# QSFP.net
KiCad netlist of a schematic drawn in Altium Designer
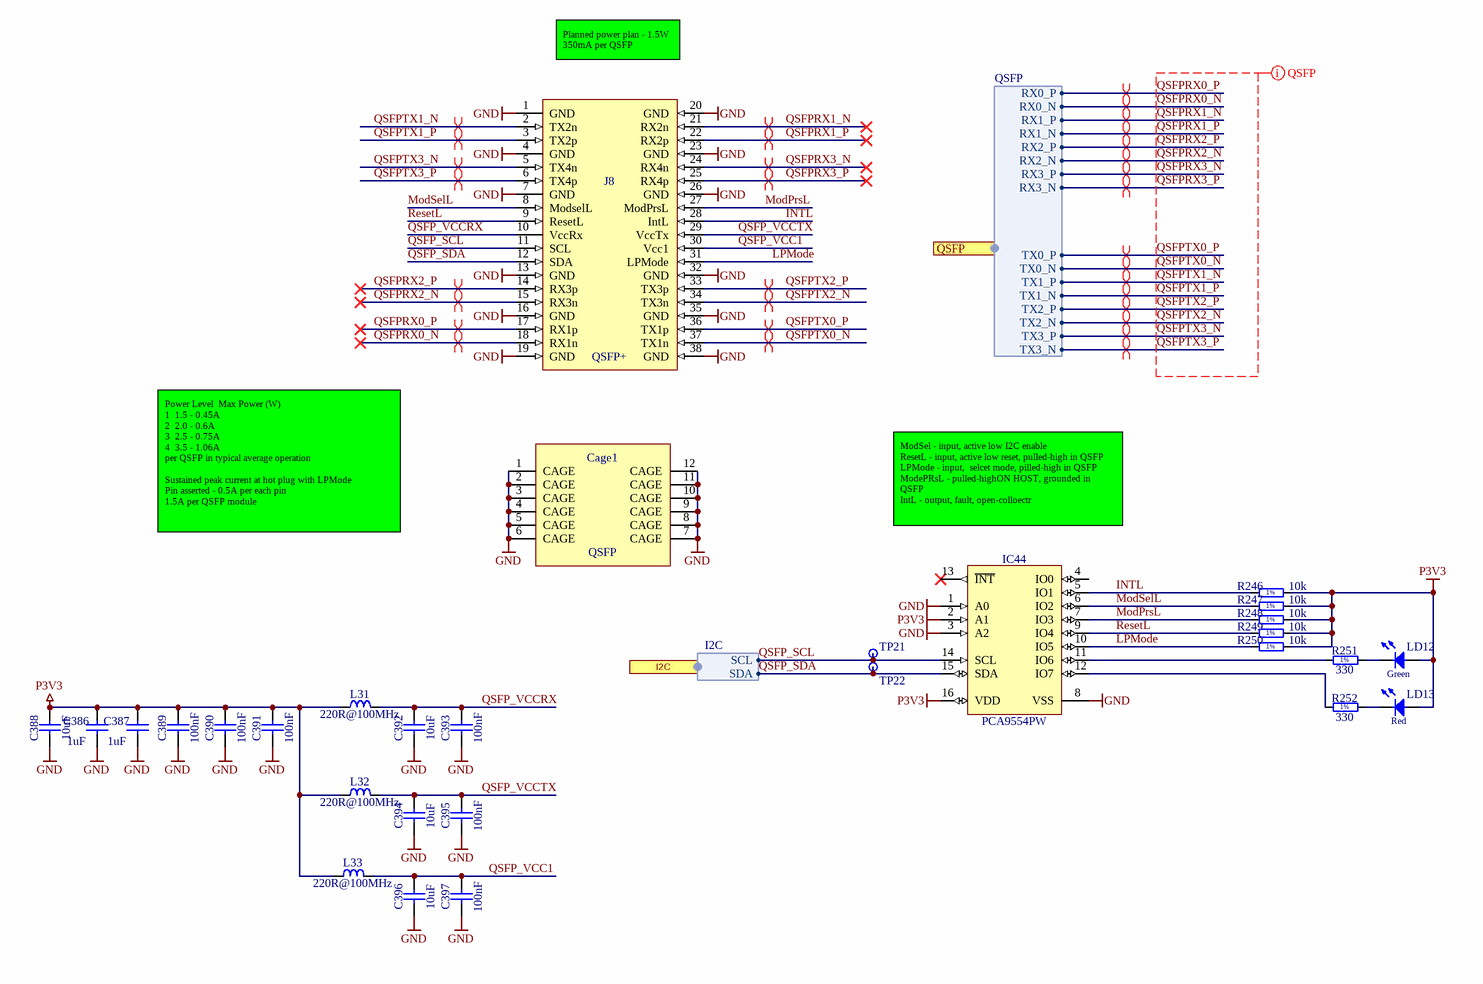
[diagram p0: QSFP.SchDoc]

(export (version "E")
  (design (tool "Eeschema 10.0.6"))
  (components
    (comp (ref "C386")
      (value "1uF")
      (footprint "CAPC1005X55N")
      (description "Non-polarised capacitor")
      (fields
        (field (name "MANUFACTURER PART NUMBER") "CC0402_1UF_16V_10%_X5R")
        (field (name "MANUFACTURER") "GENERIC")
        (field (name "AUTHOR") "CERN DEM JLC")
      )
      (libsource (lib "Capacitors") (part "Capacitor - non polarized"))
    )
    (comp (ref "C387")
      (value "1uF")
      (footprint "CAPC1005X55N")
      (description "Non-polarised capacitor")
      (fields
        (field (name "MANUFACTURER PART NUMBER") "CC0402_1UF_16V_10%_X5R")
        (field (name "MANUFACTURER") "GENERIC")
        (field (name "AUTHOR") "CERN DEM JLC")
      )
      (libsource (lib "Capacitors") (part "Capacitor - non polarized"))
    )
    (comp (ref "C388")
      (value "10uF")
      (footprint "CAPC2012X135N")
      (description "Non-polarised capacitor")
      (fields
        (field (name "PART NUMBER") "CC0805_10UF_10V_10%_X7R")
        (field (name "VOLTAGE") "10V")
        (field (name "AUTHOR") "CERN DEM JLC")
      )
      (libsource (lib "Capacitors") (part "Capacitor - non polarized"))
    )
    (comp (ref "C389")
      (value "100nF")
      (footprint "CAPC1005X55N")
      (description "Non-polarised capacitor")
      (fields
        (field (name "PART NUMBER") "CC0402_100NF_16V_10%_X5R")
        (field (name "VOLTAGE") "16V")
        (field (name "AUTHOR") "CERN DEM JLC")
      )
      (libsource (lib "Capacitors") (part "Capacitor - non polarized"))
    )
    (comp (ref "C390")
      (value "100nF")
      (footprint "CAPC1005X55N")
      (description "Non-polarised capacitor")
      (fields
        (field (name "PART NUMBER") "CC0402_100NF_16V_10%_X5R")
        (field (name "VOLTAGE") "16V")
        (field (name "AUTHOR") "CERN DEM JLC")
      )
      (libsource (lib "Capacitors") (part "Capacitor - non polarized"))
    )
    (comp (ref "C391")
      (value "100nF")
      (footprint "CAPC1005X55N")
      (description "Non-polarised capacitor")
      (fields
        (field (name "PART NUMBER") "CC0402_100NF_16V_10%_X5R")
        (field (name "VOLTAGE") "16V")
        (field (name "AUTHOR") "CERN DEM JLC")
      )
      (libsource (lib "Capacitors") (part "Capacitor - non polarized"))
    )
    (comp (ref "C392")
      (value "10uF")
      (footprint "CAPC2012X135N")
      (description "Non-polarised capacitor")
      (fields
        (field (name "PART NUMBER") "CC0805_10UF_10V_10%_X7R")
        (field (name "VOLTAGE") "10V")
        (field (name "AUTHOR") "CERN DEM JLC")
      )
      (libsource (lib "Capacitors") (part "Capacitor - non polarized"))
    )
    (comp (ref "C393")
      (value "100nF")
      (footprint "CAPC1005X55N")
      (description "Non-polarised capacitor")
      (fields
        (field (name "PART NUMBER") "CC0402_100NF_16V_10%_X5R")
        (field (name "VOLTAGE") "16V")
        (field (name "AUTHOR") "CERN DEM JLC")
      )
      (libsource (lib "Capacitors") (part "Capacitor - non polarized"))
    )
    (comp (ref "C394")
      (value "10uF")
      (footprint "CAPC2012X135N")
      (description "Non-polarised capacitor")
      (fields
        (field (name "PART NUMBER") "CC0805_10UF_10V_10%_X7R")
        (field (name "VOLTAGE") "10V")
        (field (name "AUTHOR") "CERN DEM JLC")
      )
      (libsource (lib "Capacitors") (part "Capacitor - non polarized"))
    )
    (comp (ref "C395")
      (value "100nF")
      (footprint "CAPC1005X55N")
      (description "Non-polarised capacitor")
      (fields
        (field (name "PART NUMBER") "CC0402_100NF_16V_10%_X5R")
        (field (name "VOLTAGE") "16V")
        (field (name "AUTHOR") "CERN DEM JLC")
      )
      (libsource (lib "Capacitors") (part "Capacitor - non polarized"))
    )
    (comp (ref "C396")
      (value "10uF")
      (footprint "CAPC2012X135N")
      (description "Non-polarised capacitor")
      (fields
        (field (name "PART NUMBER") "CC0805_10UF_10V_10%_X7R")
        (field (name "VOLTAGE") "10V")
        (field (name "AUTHOR") "CERN DEM JLC")
      )
      (libsource (lib "Capacitors") (part "Capacitor - non polarized"))
    )
    (comp (ref "C397")
      (value "100nF")
      (footprint "CAPC1005X55N")
      (description "Non-polarised capacitor")
      (fields
        (field (name "PART NUMBER") "CC0402_100NF_16V_10%_X5R")
        (field (name "VOLTAGE") "16V")
        (field (name "AUTHOR") "CERN DEM JLC")
      )
      (libsource (lib "Capacitors") (part "Capacitor - non polarized"))
    )
    (comp (ref "Cage1")
      (value "QSFP")
      (footprint "TYCO_1888617-1")
      (description "QSFP 1x1 Cage (12Pins)")
      (fields
        (field (name "PART NUMBER") "TYCO_1888617-1")
        (field (name "MANUFACTURER") "TYCO ELECTRONICS")
        (field (name "AUTHOR") "CERN DEM JLC")
      )
      (libsource (lib "Connectors") (part "QSFP 1x1 Cage (12Pins)"))
    )
    (comp (ref "IC44")
      (value "PCA9554PW")
      (footprint "SOP65P640X110-16N")
      (description "8-Bit I2C-Bus and SMBus I/O Port with Interrupt")
      (fields (field (name "MANUFACTURER") "NXP SEMICONDUCTORS") (field (name "AUTHOR") "CERN DEM JLC"))
      (libsource (lib "ICs And Semiconductors") (part "PCA9554PW"))
    )
    (comp (ref "J8")
      (value "QSFP+")
      (footprint "TYCO_2110819-1")
      (description "38Position QSFP Connector  (Quad Small Form-factor Pluggable)")
      (fields
        (field (name "PART NUMBER") "TYCO_2110819-1")
        (field (name "MANUFACTURER") "TYCO ELECTRONICS")
        (field (name "AUTHOR") "CERN DEM JLC")
      )
      (libsource (lib "Connectors") (part "QSFP+x1"))
    )
    (comp (ref "L31")
      (value "220R@100MHz")
      (footprint "INDC2012X105N")
      (description "Inductor")
      (fields
        (field (name "PART NUMBER") "IND0805_MURATA_BLM21PG221SN1D")
        (field (name "POWER") "2A")
        (field (name "AUTHOR") "CERN DEM JLC")
      )
      (libsource (lib "Inductors & Transformers") (part "Inductor"))
    )
    (comp (ref "L32")
      (value "220R@100MHz")
      (footprint "INDC2012X105N")
      (description "Inductor")
      (fields
        (field (name "PART NUMBER") "IND0805_MURATA_BLM21PG221SN1D")
        (field (name "POWER") "2A")
        (field (name "AUTHOR") "CERN DEM JLC")
      )
      (libsource (lib "Inductors & Transformers") (part "Inductor"))
    )
    (comp (ref "L33")
      (value "220R@100MHz")
      (footprint "INDC2012X105N")
      (description "Inductor")
      (fields
        (field (name "PART NUMBER") "IND0805_MURATA_BLM21PG221SN1D")
        (field (name "POWER") "2A")
        (field (name "AUTHOR") "CERN DEM JLC")
      )
      (libsource (lib "Inductors & Transformers") (part "Inductor"))
    )
    (comp (ref "LD12")
      (value "Green")
      (footprint "LED_AVAGO_HSME-C120")
      (description "LED Green 1C 2A")
      (fields
        (field (name "MANUFACTURER PART NUMBER") "HSME-C120")
        (field (name "MANUFACTURER") "AVAGO TECHNOLOGIES")
        (field (name "AUTHOR") "CERN DEM JMW")
      )
      (libsource (lib "ICs And Semiconductors") (part "LED Green 1C 2A"))
    )
    (comp (ref "LD13")
      (value "Red")
      (footprint "LED_AVAGO_HSMC-C120")
      (description "LED Red 1C 2A")
      (fields
        (field (name "PART NUMBER") "LED_AVAGO_HSMC-C120")
        (field (name "MANUFACTURER") "AVAGO TECHNOLOGIES")
        (field (name "AUTHOR") "CERN DEM JMW")
      )
      (libsource (lib "ICs And Semiconductors") (part "LED Red 1C 2A"))
    )
    (comp (ref "R246")
      (value "10k")
      (footprint "RESC1005X40N")
      (description "Resistor - 1%")
      (fields
        (field (name "MANUFACTURER PART NUMBER") "R0402_10K_1%_0.0625W_100PPM")
        (field (name "MANUFACTURER") "GENERIC")
        (field (name "AUTHOR") "CERN DEM JLC")
      )
      (libsource (lib "Resistors") (part "Resistor - 1%"))
    )
    (comp (ref "R247")
      (value "10k")
      (footprint "RESC1005X40N")
      (description "Resistor - 1%")
      (fields
        (field (name "MANUFACTURER PART NUMBER") "R0402_10K_1%_0.0625W_100PPM")
        (field (name "MANUFACTURER") "GENERIC")
        (field (name "AUTHOR") "CERN DEM JLC")
      )
      (libsource (lib "Resistors") (part "Resistor - 1%"))
    )
    (comp (ref "R248")
      (value "10k")
      (footprint "RESC1005X40N")
      (description "Resistor - 1%")
      (fields
        (field (name "MANUFACTURER PART NUMBER") "R0402_10K_1%_0.0625W_100PPM")
        (field (name "MANUFACTURER") "GENERIC")
        (field (name "AUTHOR") "CERN DEM JLC")
      )
      (libsource (lib "Resistors") (part "Resistor - 1%"))
    )
    (comp (ref "R249")
      (value "10k")
      (footprint "RESC1005X40N")
      (description "Resistor - 1%")
      (fields
        (field (name "MANUFACTURER PART NUMBER") "R0402_10K_1%_0.0625W_100PPM")
        (field (name "MANUFACTURER") "GENERIC")
        (field (name "AUTHOR") "CERN DEM JLC")
      )
      (libsource (lib "Resistors") (part "Resistor - 1%"))
    )
    (comp (ref "R250")
      (value "10k")
      (footprint "RESC1005X40N")
      (description "Resistor - 1%")
      (fields
        (field (name "MANUFACTURER PART NUMBER") "R0402_10K_1%_0.0625W_100PPM")
        (field (name "MANUFACTURER") "GENERIC")
        (field (name "AUTHOR") "CERN DEM JLC")
      )
      (libsource (lib "Resistors") (part "Resistor - 1%"))
    )
    (comp (ref "R251")
      (value "330")
      (footprint "RESC1005X40N")
      (description "Resistor - 1%")
      (fields
        (field (name "MANUFACTURER PART NUMBER") "R0402_330R_1%_0.0625W_100PPM")
        (field (name "MANUFACTURER") "GENERIC")
        (field (name "AUTHOR") "CERN DEM JLC")
      )
      (libsource (lib "Resistors") (part "Resistor - 1%"))
    )
    (comp (ref "R252")
      (value "330")
      (footprint "RESC1005X40N")
      (description "Resistor - 1%")
      (fields
        (field (name "MANUFACTURER PART NUMBER") "R0402_330R_1%_0.0625W_100PPM")
        (field (name "MANUFACTURER") "GENERIC")
        (field (name "AUTHOR") "CERN DEM JLC")
      )
      (libsource (lib "Resistors") (part "Resistor - 1%"))
    )
    (comp (ref "TP21")
      (value "Test Point")
      (footprint "TPS127")
      (fields (field (name "PART NUMBER") "SMD_PAD_1.27X1.27MM") (field (name "AUTHOR") "CERN DEM JLC"))
      (libsource (lib "Eletro-mechanical") (part "Test Point"))
    )
    (comp (ref "TP22")
      (value "Test Point")
      (footprint "TPS127")
      (fields (field (name "PART NUMBER") "SMD_PAD_1.27X1.27MM") (field (name "AUTHOR") "CERN DEM JLC"))
      (libsource (lib "Eletro-mechanical") (part "Test Point"))
    )
  )
  (nets
    (net (code "3") (name "/INTL") (class "Default")
      (node (ref "IC44") (pin "5") (pinfunction "IO1_5") (pintype "bidirectional"))
      (node (ref "J8") (pin "28") (pinfunction "IntL_28") (pintype "input"))
      (node (ref "R246") (pin "1") (pinfunction "1_1") (pintype "passive"))
    )
    (net (code "4") (name "/LPMode") (class "Default")
      (node (ref "IC44") (pin "10") (pinfunction "IO5_10") (pintype "bidirectional"))
      (node (ref "J8") (pin "31") (pinfunction "LPMode_31") (pintype "input"))
      (node (ref "R250") (pin "1") (pinfunction "1_1") (pintype "passive"))
    )
    (net (code "5") (name "/ModPrsL") (class "Default")
      (node (ref "IC44") (pin "7") (pinfunction "IO3_7") (pintype "bidirectional"))
      (node (ref "J8") (pin "27") (pinfunction "ModPrsL_27") (pintype "input"))
      (node (ref "R248") (pin "1") (pinfunction "1_1") (pintype "passive"))
    )
    (net (code "6") (name "/ModSelL") (class "Default")
      (node (ref "IC44") (pin "6") (pinfunction "IO2_6") (pintype "bidirectional"))
      (node (ref "J8") (pin "8") (pinfunction "ModselL_8") (pintype "input"))
      (node (ref "R247") (pin "1") (pinfunction "1_1") (pintype "passive"))
    )
    (net (code "7") (name "/QSFPRX0_N") (class "Default")
      (node (ref "J8") (pin "18") (pinfunction "RX1n_18") (pintype "input+no_connect"))
    )
    (net (code "8") (name "/QSFPRX0_P") (class "Default")
      (node (ref "J8") (pin "17") (pinfunction "RX1p_17") (pintype "input+no_connect"))
    )
    (net (code "9") (name "/QSFPRX1_N") (class "Default")
      (node (ref "J8") (pin "21") (pinfunction "RX2n_21") (pintype "input+no_connect"))
    )
    (net (code "10") (name "/QSFPRX1_P") (class "Default")
      (node (ref "J8") (pin "22") (pinfunction "RX2p_22") (pintype "input+no_connect"))
    )
    (net (code "11") (name "/QSFPRX2_N") (class "Default")
      (node (ref "J8") (pin "15") (pinfunction "RX3n_15") (pintype "input+no_connect"))
    )
    (net (code "12") (name "/QSFPRX2_P") (class "Default")
      (node (ref "J8") (pin "14") (pinfunction "RX3p_14") (pintype "input+no_connect"))
    )
    (net (code "13") (name "/QSFPRX3_N") (class "Default")
      (node (ref "J8") (pin "24") (pinfunction "RX4n_24") (pintype "input"))
    )
    (net (code "14") (name "/QSFPRX3_P") (class "Default")
      (node (ref "J8") (pin "25") (pinfunction "RX4p_25") (pintype "input+no_connect"))
    )
    (net (code "15") (name "/QSFPTX0_N") (class "Default")
      (node (ref "J8") (pin "37") (pinfunction "TX1n_37") (pintype "input"))
    )
    (net (code "16") (name "/QSFPTX0_P") (class "Default")
      (node (ref "J8") (pin "36") (pinfunction "TX1p_36") (pintype "input"))
    )
    (net (code "17") (name "/QSFPTX1_N") (class "Default")
      (node (ref "J8") (pin "2") (pinfunction "TX2n_2") (pintype "input"))
    )
    (net (code "18") (name "/QSFPTX1_P") (class "Default")
      (node (ref "J8") (pin "3") (pinfunction "TX2p_3") (pintype "input"))
    )
    (net (code "19") (name "/QSFPTX2_N") (class "Default")
      (node (ref "J8") (pin "34") (pinfunction "TX3n_34") (pintype "input"))
    )
    (net (code "20") (name "/QSFPTX2_P") (class "Default")
      (node (ref "J8") (pin "33") (pinfunction "TX3p_33") (pintype "input"))
    )
    (net (code "21") (name "/QSFPTX3_N") (class "Default")
      (node (ref "J8") (pin "5") (pinfunction "TX4n_5") (pintype "input"))
    )
    (net (code "22") (name "/QSFPTX3_P") (class "Default")
      (node (ref "J8") (pin "6") (pinfunction "TX4p_6") (pintype "input"))
    )
    (net (code "23") (name "/QSFP_SCL") (class "Default")
      (node (ref "IC44") (pin "14") (pinfunction "SCL_14") (pintype "input"))
      (node (ref "J8") (pin "11") (pinfunction "SCL_11") (pintype "input"))
      (node (ref "TP21") (pin "1") (pinfunction "1_1") (pintype "bidirectional"))
    )
    (net (code "24") (name "/QSFP_SDA") (class "Default")
      (node (ref "IC44") (pin "15") (pinfunction "SDA_15") (pintype "bidirectional"))
      (node (ref "J8") (pin "12") (pinfunction "SDA_12") (pintype "input"))
      (node (ref "TP22") (pin "1") (pinfunction "1_1") (pintype "bidirectional"))
    )
    (net (code "25") (name "/QSFP_VCC1") (class "Default")
      (node (ref "C396") (pin "2") (pinfunction "2_2") (pintype "passive"))
      (node (ref "C397") (pin "2") (pinfunction "2_2") (pintype "passive"))
      (node (ref "J8") (pin "30") (pinfunction "Vcc1_30") (pintype "input"))
      (node (ref "L33") (pin "2") (pinfunction "2_2") (pintype "passive"))
    )
    (net (code "26") (name "/QSFP_VCCRX") (class "Default")
      (node (ref "C392") (pin "2") (pinfunction "2_2") (pintype "passive"))
      (node (ref "C393") (pin "2") (pinfunction "2_2") (pintype "passive"))
      (node (ref "J8") (pin "10") (pinfunction "VccRx_10") (pintype "power_in"))
      (node (ref "L31") (pin "2") (pinfunction "2_2") (pintype "passive"))
    )
    (net (code "27") (name "/QSFP_VCCTX") (class "Default")
      (node (ref "C394") (pin "2") (pinfunction "2_2") (pintype "passive"))
      (node (ref "C395") (pin "2") (pinfunction "2_2") (pintype "passive"))
      (node (ref "J8") (pin "29") (pinfunction "VccTx_29") (pintype "input"))
      (node (ref "L32") (pin "2") (pinfunction "2_2") (pintype "passive"))
    )
    (net (code "28") (name "/ResetL") (class "Default")
      (node (ref "IC44") (pin "9") (pinfunction "IO4_9") (pintype "bidirectional"))
      (node (ref "J8") (pin "9") (pinfunction "ResetL_9") (pintype "input"))
      (node (ref "R249") (pin "1") (pinfunction "1_1") (pintype "passive"))
    )
    (net (code "31") (name "GND") (class "Default")
      (node (ref "C386") (pin "2") (pinfunction "2_2") (pintype "passive"))
      (node (ref "C387") (pin "2") (pinfunction "2_2") (pintype "passive"))
      (node (ref "C388") (pin "1") (pinfunction "1_1") (pintype "passive"))
      (node (ref "C389") (pin "1") (pinfunction "1_1") (pintype "passive"))
      (node (ref "C390") (pin "1") (pinfunction "1_1") (pintype "passive"))
      (node (ref "C391") (pin "1") (pinfunction "1_1") (pintype "passive"))
      (node (ref "C392") (pin "1") (pinfunction "1_1") (pintype "passive"))
      (node (ref "C393") (pin "1") (pinfunction "1_1") (pintype "passive"))
      (node (ref "C394") (pin "1") (pinfunction "1_1") (pintype "passive"))
      (node (ref "C395") (pin "1") (pinfunction "1_1") (pintype "passive"))
      (node (ref "C396") (pin "1") (pinfunction "1_1") (pintype "passive"))
      (node (ref "C397") (pin "1") (pinfunction "1_1") (pintype "passive"))
      (node (ref "Cage1") (pin "1") (pinfunction "CAGE_1") (pintype "power_in"))
      (node (ref "Cage1") (pin "10") (pinfunction "CAGE_10") (pintype "power_in"))
      (node (ref "Cage1") (pin "11") (pinfunction "CAGE_11") (pintype "power_in"))
      (node (ref "Cage1") (pin "12") (pinfunction "CAGE_12") (pintype "power_in"))
      (node (ref "Cage1") (pin "2") (pinfunction "CAGE_2") (pintype "power_in"))
      (node (ref "Cage1") (pin "3") (pinfunction "CAGE_3") (pintype "power_in"))
      (node (ref "Cage1") (pin "4") (pinfunction "CAGE_4") (pintype "power_in"))
      (node (ref "Cage1") (pin "5") (pinfunction "CAGE_5") (pintype "power_in"))
      (node (ref "Cage1") (pin "6") (pinfunction "CAGE_6") (pintype "power_in"))
      (node (ref "Cage1") (pin "7") (pinfunction "CAGE_7") (pintype "power_in"))
      (node (ref "Cage1") (pin "8") (pinfunction "CAGE_8") (pintype "power_in"))
      (node (ref "Cage1") (pin "9") (pinfunction "CAGE_9") (pintype "power_in"))
      (node (ref "IC44") (pin "1") (pinfunction "A0_1") (pintype "input"))
      (node (ref "IC44") (pin "3") (pinfunction "A2_3") (pintype "input"))
      (node (ref "IC44") (pin "8") (pinfunction "VSS_8") (pintype "power_in"))
      (node (ref "J8") (pin "1") (pinfunction "GND_1") (pintype "power_in"))
      (node (ref "J8") (pin "13") (pinfunction "GND_13") (pintype "input"))
      (node (ref "J8") (pin "16") (pinfunction "GND_16") (pintype "input"))
      (node (ref "J8") (pin "19") (pinfunction "GND_19") (pintype "input"))
      (node (ref "J8") (pin "20") (pinfunction "GND_20") (pintype "input"))
      (node (ref "J8") (pin "23") (pinfunction "GND_23") (pintype "input"))
      (node (ref "J8") (pin "26") (pinfunction "GND_26") (pintype "input"))
      (node (ref "J8") (pin "32") (pinfunction "GND_32") (pintype "input"))
      (node (ref "J8") (pin "35") (pinfunction "GND_35") (pintype "input"))
      (node (ref "J8") (pin "38") (pinfunction "GND_38") (pintype "input"))
      (node (ref "J8") (pin "4") (pinfunction "GND_4") (pintype "power_in"))
      (node (ref "J8") (pin "7") (pinfunction "GND_7") (pintype "power_in"))
    )
    (net (code "32") (name "Net-(IC44-IO6)") (class "Default")
      (node (ref "IC44") (pin "11") (pinfunction "IO6_11") (pintype "bidirectional"))
      (node (ref "R251") (pin "1") (pinfunction "1_1") (pintype "passive"))
    )
    (net (code "33") (name "Net-(IC44-IO7)") (class "Default")
      (node (ref "IC44") (pin "12") (pinfunction "IO7_12") (pintype "bidirectional"))
      (node (ref "R252") (pin "1") (pinfunction "1_1") (pintype "passive"))
    )
    (net (code "34") (name "Net-(LD12-C)") (class "Default")
      (node (ref "LD12") (pin "1") (pinfunction "C_1") (pintype "passive"))
      (node (ref "R251") (pin "2") (pinfunction "2_2") (pintype "passive"))
    )
    (net (code "35") (name "Net-(LD13-C)") (class "Default")
      (node (ref "LD13") (pin "1") (pinfunction "C_1") (pintype "passive"))
      (node (ref "R252") (pin "2") (pinfunction "2_2") (pintype "passive"))
    )
    (net (code "36") (name "P3V3") (class "Default")
      (node (ref "C386") (pin "1") (pinfunction "1_1") (pintype "passive"))
      (node (ref "C387") (pin "1") (pinfunction "1_1") (pintype "passive"))
      (node (ref "C388") (pin "2") (pinfunction "2_2") (pintype "passive"))
      (node (ref "C389") (pin "2") (pinfunction "2_2") (pintype "passive"))
      (node (ref "C390") (pin "2") (pinfunction "2_2") (pintype "passive"))
      (node (ref "C391") (pin "2") (pinfunction "2_2") (pintype "passive"))
      (node (ref "IC44") (pin "16") (pinfunction "VDD_16") (pintype "bidirectional"))
      (node (ref "IC44") (pin "2") (pinfunction "A1_2") (pintype "input"))
      (node (ref "L31") (pin "1") (pinfunction "1_1") (pintype "passive"))
      (node (ref "L32") (pin "1") (pinfunction "1_1") (pintype "passive"))
      (node (ref "L33") (pin "1") (pinfunction "1_1") (pintype "passive"))
      (node (ref "LD12") (pin "2") (pinfunction "A_2") (pintype "passive"))
      (node (ref "LD13") (pin "2") (pinfunction "A_2") (pintype "passive"))
      (node (ref "R246") (pin "2") (pinfunction "2_2") (pintype "passive"))
      (node (ref "R247") (pin "2") (pinfunction "2_2") (pintype "passive"))
      (node (ref "R248") (pin "2") (pinfunction "2_2") (pintype "passive"))
      (node (ref "R249") (pin "2") (pinfunction "2_2") (pintype "passive"))
      (node (ref "R250") (pin "2") (pinfunction "2_2") (pintype "passive"))
    )
    (net (code "37") (name "unconnected-(IC44-IO0-Pad4)") (class "Default")
      (node (ref "IC44") (pin "4") (pinfunction "IO0_4") (pintype "bidirectional"))
    )
    (net (code "38") (name "unconnected-(IC44-~{INT}-Pad13)") (class "Default")
      (node (ref "IC44") (pin "13") (pinfunction "~{INT}_13") (pintype "output+no_connect"))
    )
  )
)
